# Sheet1.net
KiCad netlist of a schematic drawn in Altium Designer
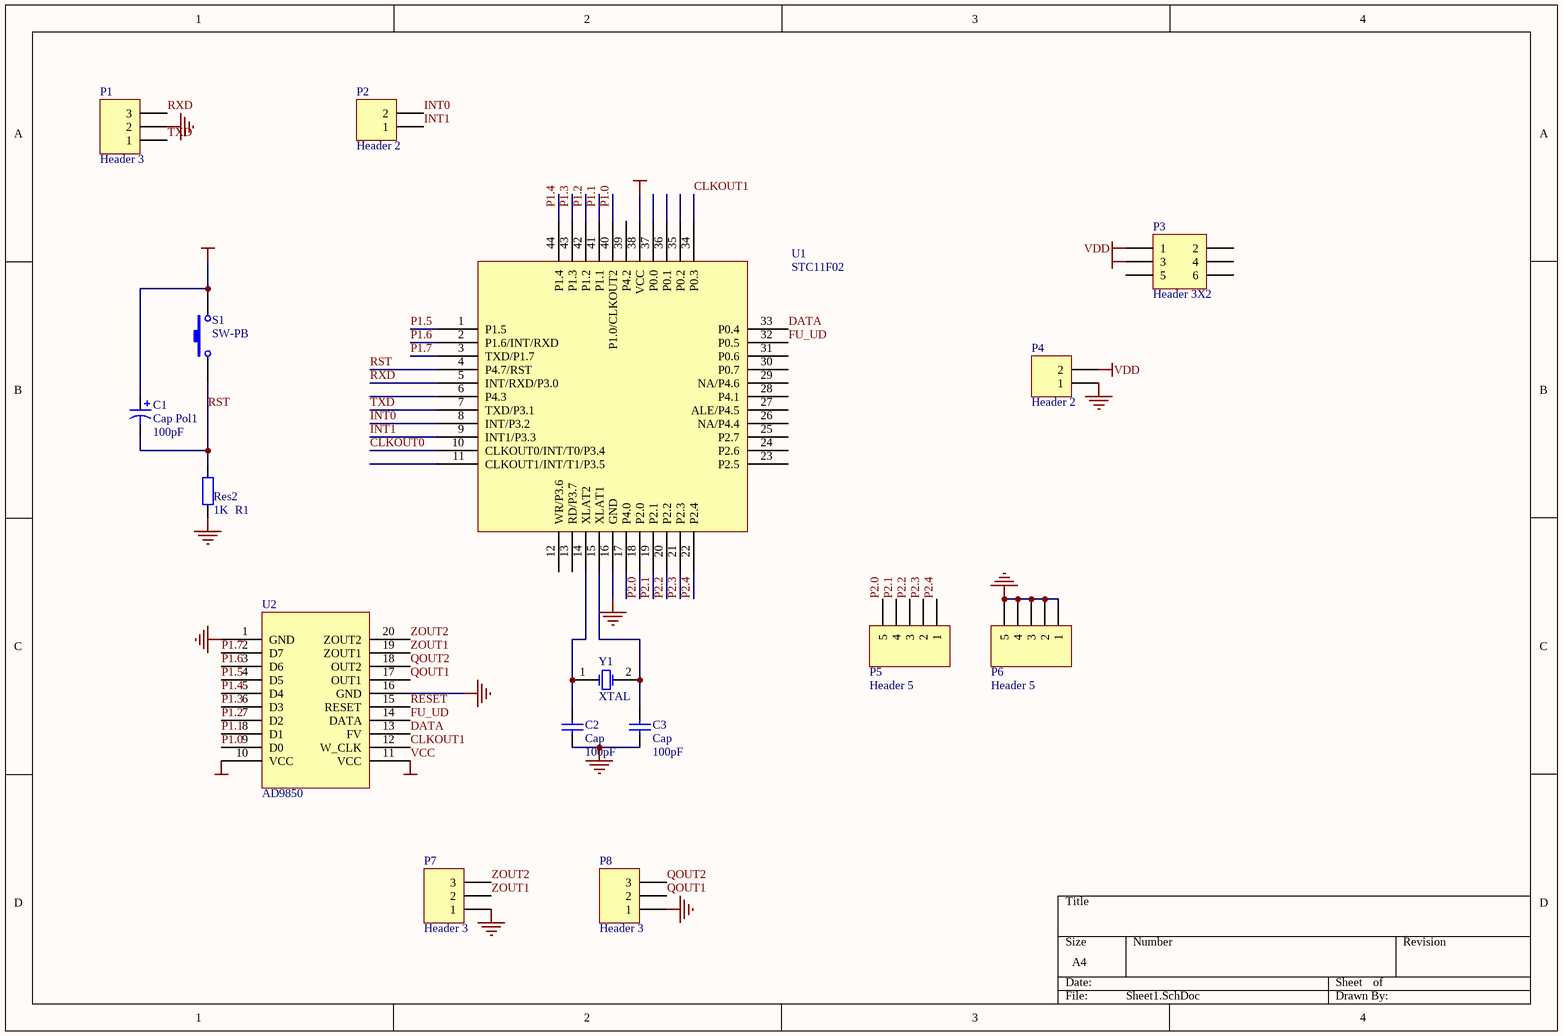
[diagram p0: Sheet1.SchDoc]

(export (version "E")
  (design (tool "Eeschema 10.0.6"))
  (components
    (comp (ref "C1")
      (value "Cap Pol1")
      (footprint "3.5X2.8X1.9")
      (description "Polarized Capacitor (Radial)")
      (fields (field (name "ALTIUM_VALUE") "100pF") (field (name "PUBLISHER") "Altium Limited"))
      (libsource (lib "Miscellaneous Devices") (part "Cap Pol1"))
    )
    (comp (ref "C2")
      (value "Cap")
      (footprint "2012[0805]")
      (description "Capacitor")
      (fields (field (name "ALTIUM_VALUE") "100pF") (field (name "PUBLISHER") "Altium Limited"))
      (libsource (lib "Miscellaneous Devices") (part "Cap"))
    )
    (comp (ref "C3")
      (value "Cap")
      (footprint "6-0805")
      (description "Capacitor")
      (fields (field (name "ALTIUM_VALUE") "100pF") (field (name "PUBLISHER") "Altium Limited"))
      (libsource (lib "Miscellaneous Devices") (part "Cap"))
    )
    (comp (ref "P1")
      (value "Header 3")
      (footprint "HDR1X3")
      (description "Header, 3-Pin")
      (fields (field (name "PUBLISHER") "Altium Limited"))
      (libsource (lib "Miscellaneous Connectors") (part "Header 3"))
    )
    (comp (ref "P2")
      (value "Header 2")
      (footprint "HDR1X2")
      (description "Header, 2-Pin")
      (fields (field (name "PUBLISHER") "Altium Limited"))
      (libsource (lib "Miscellaneous Connectors") (part "Header 2"))
    )
    (comp (ref "P3")
      (value "Header 3X2")
      (footprint "KZ")
      (description "Header, 3-Pin, Dual row")
      (fields (field (name "PUBLISHER") "Altium Limited"))
      (libsource (lib "Miscellaneous Connectors") (part "Header 3X2"))
    )
    (comp (ref "P4")
      (value "Header 2")
      (footprint "HDR1X2")
      (description "Header, 2-Pin")
      (fields (field (name "PUBLISHER") "Altium Limited"))
      (libsource (lib "Miscellaneous Connectors") (part "Header 2"))
    )
    (comp (ref "P5")
      (value "Header 5")
      (footprint "HDR1X5")
      (description "Header, 5-Pin")
      (fields (field (name "PUBLISHER") "Altium Limited"))
      (libsource (lib "Miscellaneous Connectors") (part "Header 5"))
    )
    (comp (ref "P6")
      (value "Header 5")
      (footprint "HDR1X5")
      (description "Header, 5-Pin")
      (fields (field (name "PUBLISHER") "Altium Limited"))
      (libsource (lib "Miscellaneous Connectors") (part "Header 5"))
    )
    (comp (ref "P7")
      (value "Header 3")
      (footprint "HDR1X3")
      (description "Header, 3-Pin")
      (fields (field (name "PUBLISHER") "Altium Limited"))
      (libsource (lib "Miscellaneous Connectors") (part "Header 3"))
    )
    (comp (ref "P8")
      (value "Header 3")
      (footprint "HDR1X3")
      (description "Header, 3-Pin")
      (fields (field (name "PUBLISHER") "Altium Limited"))
      (libsource (lib "Miscellaneous Connectors") (part "Header 3"))
    )
    (comp (ref "R1")
      (value "Res2")
      (footprint "6-0805")
      (description "Resistor")
      (fields (field (name "ALTIUM_VALUE") "1K") (field (name "PUBLISHER") "Altium Limited"))
      (libsource (lib "Miscellaneous Devices") (part "Res2"))
    )
    (comp (ref "S1")
      (value "SW-PB")
      (footprint "按键")
      (description "Switch")
      (fields (field (name "PUBLISHER") "Altium Limited"))
      (libsource (lib "Miscellaneous Devices") (part "SW-PB"))
    )
    (comp (ref "U1") (value "STC11F02") (footprint "LQLPF44") (libsource (lib "STC_sch") (part "STC11F02")))
    (comp (ref "U2") (value "AD9850") (footprint "ADMK") (libsource (lib "STC_sch") (part "AD9850")))
    (comp (ref "Y1")
      (value "XTAL")
      (footprint "XTAL-200mil")
      (description "Crystal Oscillator")
      (fields (field (name "PUBLISHER") "Altium Limited"))
      (libsource (lib "Miscellaneous Devices") (part "XTAL"))
    )
  )
  (nets
    (net (code "1") (name "+5") (class "Default")
      (node (ref "C1") (pin "1") (pinfunction "1_1") (pintype "passive"))
      (node (ref "P3") (pin "3") (pinfunction "3_3") (pintype "passive"))
      (node (ref "S1") (pin "2") (pinfunction "2_2") (pintype "passive"))
      (node (ref "U1") (pin "38") (pinfunction "VCC_38") (pintype "passive"))
      (node (ref "U2") (pin "10") (pinfunction "VCC_10") (pintype "passive"))
      (node (ref "U2") (pin "11") (pinfunction "VCC_11") (pintype "passive"))
    )
    (net (code "2") (name "/CLKOUT0") (class "Default")
      (node (ref "U1") (pin "10") (pinfunction "CLKOUT0/INT/T0/P3.4_10") (pintype "passive"))
    )
    (net (code "3") (name "/CLKOUT1") (class "Default")
      (node (ref "U1") (pin "34") (pinfunction "P0.3_34") (pintype "passive"))
      (node (ref "U2") (pin "12") (pinfunction "W_CLK_12") (pintype "passive"))
    )
    (net (code "4") (name "/DATA") (class "Default")
      (node (ref "U1") (pin "33") (pinfunction "P0.4_33") (pintype "passive"))
      (node (ref "U2") (pin "13") (pinfunction "FV_13") (pintype "passive"))
    )
    (net (code "5") (name "/FU_UD") (class "Default")
      (node (ref "U1") (pin "32") (pinfunction "P0.5_32") (pintype "passive"))
      (node (ref "U2") (pin "14") (pinfunction "DATA_14") (pintype "passive"))
    )
    (net (code "6") (name "/INT0") (class "Default")
      (node (ref "P2") (pin "2") (pinfunction "2_2") (pintype "passive"))
      (node (ref "U1") (pin "8") (pinfunction "INT/P3.2_8") (pintype "passive"))
    )
    (net (code "7") (name "/INT1") (class "Default")
      (node (ref "P2") (pin "1") (pinfunction "1_1") (pintype "passive"))
      (node (ref "U1") (pin "9") (pinfunction "INT1/P3.3_9") (pintype "passive"))
    )
    (net (code "8") (name "/P1.0") (class "Default")
      (node (ref "U1") (pin "40") (pinfunction "P1.0/CLKOUT2_40") (pintype "passive"))
      (node (ref "U2") (pin "9") (pinfunction "D0_9") (pintype "passive"))
    )
    (net (code "9") (name "/P1.1") (class "Default")
      (node (ref "U1") (pin "41") (pinfunction "P1.1_41") (pintype "passive"))
      (node (ref "U2") (pin "8") (pinfunction "D1_8") (pintype "passive"))
    )
    (net (code "10") (name "/P1.2") (class "Default")
      (node (ref "U1") (pin "42") (pinfunction "P1.2_42") (pintype "passive"))
      (node (ref "U2") (pin "7") (pinfunction "D2_7") (pintype "passive"))
    )
    (net (code "11") (name "/P1.3") (class "Default")
      (node (ref "U1") (pin "43") (pinfunction "P1.3_43") (pintype "passive"))
      (node (ref "U2") (pin "6") (pinfunction "D3_6") (pintype "passive"))
    )
    (net (code "12") (name "/P1.4") (class "Default")
      (node (ref "U1") (pin "44") (pinfunction "P1.4_44") (pintype "passive"))
      (node (ref "U2") (pin "5") (pinfunction "D4_5") (pintype "passive"))
    )
    (net (code "13") (name "/P1.5") (class "Default")
      (node (ref "U1") (pin "1") (pinfunction "P1.5_1") (pintype "passive"))
      (node (ref "U2") (pin "4") (pinfunction "D5_4") (pintype "passive"))
    )
    (net (code "14") (name "/P1.6") (class "Default")
      (node (ref "U1") (pin "2") (pinfunction "P1.6/INT/RXD_2") (pintype "passive"))
      (node (ref "U2") (pin "3") (pinfunction "D6_3") (pintype "passive"))
    )
    (net (code "15") (name "/P1.7") (class "Default")
      (node (ref "U1") (pin "3") (pinfunction "TXD/P1.7_3") (pintype "passive"))
      (node (ref "U2") (pin "2") (pinfunction "D7_2") (pintype "passive"))
    )
    (net (code "16") (name "/P2.0") (class "Default")
      (node (ref "P5") (pin "5") (pinfunction "5_5") (pintype "passive"))
      (node (ref "U1") (pin "18") (pinfunction "P2.0_18") (pintype "passive"))
    )
    (net (code "17") (name "/P2.1") (class "Default")
      (node (ref "P5") (pin "4") (pinfunction "4_4") (pintype "passive"))
      (node (ref "U1") (pin "19") (pinfunction "P2.1_19") (pintype "passive"))
    )
    (net (code "18") (name "/P2.2") (class "Default")
      (node (ref "P5") (pin "3") (pinfunction "3_3") (pintype "passive"))
      (node (ref "U1") (pin "20") (pinfunction "P2.2_20") (pintype "passive"))
    )
    (net (code "19") (name "/P2.3") (class "Default")
      (node (ref "P5") (pin "2") (pinfunction "2_2") (pintype "passive"))
      (node (ref "U1") (pin "21") (pinfunction "P2.3_21") (pintype "passive"))
    )
    (net (code "20") (name "/P2.4") (class "Default")
      (node (ref "P5") (pin "1") (pinfunction "1_1") (pintype "passive"))
      (node (ref "U1") (pin "22") (pinfunction "P2.4_22") (pintype "passive"))
    )
    (net (code "21") (name "/QOUT1") (class "Default")
      (node (ref "P8") (pin "2") (pinfunction "2_2") (pintype "passive"))
      (node (ref "U2") (pin "17") (pinfunction "OUT1_17") (pintype "passive"))
    )
    (net (code "22") (name "/QOUT2") (class "Default")
      (node (ref "P8") (pin "3") (pinfunction "3_3") (pintype "passive"))
      (node (ref "U2") (pin "18") (pinfunction "OUT2_18") (pintype "passive"))
    )
    (net (code "23") (name "/RESET") (class "Default")
      (node (ref "U2") (pin "15") (pinfunction "RESET_15") (pintype "passive"))
    )
    (net (code "24") (name "/RST") (class "Default")
      (node (ref "C1") (pin "2") (pinfunction "2_2") (pintype "passive"))
      (node (ref "R1") (pin "2") (pinfunction "2_2") (pintype "passive"))
      (node (ref "S1") (pin "1") (pinfunction "1_1") (pintype "passive"))
      (node (ref "U1") (pin "4") (pinfunction "P4.7/RST_4") (pintype "passive"))
    )
    (net (code "25") (name "/RXD") (class "Default")
      (node (ref "P1") (pin "3") (pinfunction "3_3") (pintype "passive"))
      (node (ref "U1") (pin "5") (pinfunction "INT/RXD/P3.0_5") (pintype "passive"))
    )
    (net (code "26") (name "/TXD") (class "Default")
      (node (ref "P1") (pin "1") (pinfunction "1_1") (pintype "passive"))
      (node (ref "U1") (pin "7") (pinfunction "TXD/P3.1_7") (pintype "passive"))
    )
    (net (code "27") (name "/ZOUT1") (class "Default")
      (node (ref "P7") (pin "2") (pinfunction "2_2") (pintype "passive"))
      (node (ref "U2") (pin "19") (pinfunction "ZOUT1_19") (pintype "passive"))
    )
    (net (code "28") (name "/ZOUT2") (class "Default")
      (node (ref "P7") (pin "3") (pinfunction "3_3") (pintype "passive"))
      (node (ref "U2") (pin "20") (pinfunction "ZOUT2_20") (pintype "passive"))
    )
    (net (code "29") (name "GND") (class "Default")
      (node (ref "C2") (pin "1") (pinfunction "1_1") (pintype "passive"))
      (node (ref "C3") (pin "1") (pinfunction "1_1") (pintype "passive"))
      (node (ref "P1") (pin "2") (pinfunction "2_2") (pintype "passive"))
      (node (ref "P4") (pin "1") (pinfunction "1_1") (pintype "passive"))
      (node (ref "P6") (pin "1") (pinfunction "1_1") (pintype "passive"))
      (node (ref "P6") (pin "2") (pinfunction "2_2") (pintype "passive"))
      (node (ref "P6") (pin "3") (pinfunction "3_3") (pintype "passive"))
      (node (ref "P6") (pin "4") (pinfunction "4_4") (pintype "passive"))
      (node (ref "P6") (pin "5") (pinfunction "5_5") (pintype "passive"))
      (node (ref "P7") (pin "1") (pinfunction "1_1") (pintype "passive"))
      (node (ref "P8") (pin "1") (pinfunction "1_1") (pintype "passive"))
      (node (ref "R1") (pin "1") (pinfunction "1_1") (pintype "passive"))
      (node (ref "U1") (pin "16") (pinfunction "GND_16") (pintype "passive"))
      (node (ref "U2") (pin "1") (pinfunction "GND_1") (pintype "passive"))
      (node (ref "U2") (pin "16") (pinfunction "GND_16") (pintype "passive"))
    )
    (net (code "30") (name "Net-(U1-XLAT1)") (class "Default")
      (node (ref "C3") (pin "2") (pinfunction "2_2") (pintype "passive"))
      (node (ref "U1") (pin "15") (pinfunction "XLAT1_15") (pintype "passive"))
      (node (ref "Y1") (pin "2") (pinfunction "OSC2_2") (pintype "passive"))
    )
    (net (code "31") (name "Net-(U1-XLAT2)") (class "Default")
      (node (ref "C2") (pin "2") (pinfunction "2_2") (pintype "passive"))
      (node (ref "U1") (pin "14") (pinfunction "XLAT2_14") (pintype "passive"))
      (node (ref "Y1") (pin "1") (pinfunction "OSC1_1") (pintype "passive"))
    )
    (net (code "32") (name "VDD") (class "Default")
      (node (ref "P3") (pin "1") (pinfunction "1_1") (pintype "passive"))
      (node (ref "P4") (pin "2") (pinfunction "2_2") (pintype "passive"))
    )
    (net (code "33") (name "unconnected-(P3-Pad2)") (class "Default")
      (node (ref "P3") (pin "2") (pinfunction "2_2") (pintype "passive"))
    )
    (net (code "34") (name "unconnected-(P3-Pad4)") (class "Default")
      (node (ref "P3") (pin "4") (pinfunction "4_4") (pintype "passive"))
    )
    (net (code "35") (name "unconnected-(P3-Pad5)") (class "Default")
      (node (ref "P3") (pin "5") (pinfunction "5_5") (pintype "passive"))
    )
    (net (code "36") (name "unconnected-(P3-Pad6)") (class "Default")
      (node (ref "P3") (pin "6") (pinfunction "6_6") (pintype "passive"))
    )
    (net (code "37") (name "unconnected-(U1-ALE{slash}P4.5-Pad27)") (class "Default")
      (node (ref "U1") (pin "27") (pinfunction "ALE/P4.5_27") (pintype "passive"))
    )
    (net (code "38") (name "unconnected-(U1-CLKOUT1{slash}INT{slash}T1{slash}P3.5-Pad11)") (class "Default")
      (node (ref "U1") (pin "11") (pinfunction "CLKOUT1/INT/T1/P3.5_11") (pintype "passive"))
    )
    (net (code "39") (name "unconnected-(U1-NA{slash}P4.4-Pad26)") (class "Default")
      (node (ref "U1") (pin "26") (pinfunction "NA/P4.4_26") (pintype "passive"))
    )
    (net (code "40") (name "unconnected-(U1-NA{slash}P4.6-Pad29)") (class "Default")
      (node (ref "U1") (pin "29") (pinfunction "NA/P4.6_29") (pintype "passive"))
    )
    (net (code "41") (name "unconnected-(U1-P0.0-Pad37)") (class "Default")
      (node (ref "U1") (pin "37") (pinfunction "P0.0_37") (pintype "passive"))
    )
    (net (code "42") (name "unconnected-(U1-P0.1-Pad36)") (class "Default")
      (node (ref "U1") (pin "36") (pinfunction "P0.1_36") (pintype "passive"))
    )
    (net (code "43") (name "unconnected-(U1-P0.2-Pad35)") (class "Default")
      (node (ref "U1") (pin "35") (pinfunction "P0.2_35") (pintype "passive"))
    )
    (net (code "44") (name "unconnected-(U1-P0.6-Pad31)") (class "Default")
      (node (ref "U1") (pin "31") (pinfunction "P0.6_31") (pintype "passive"))
    )
    (net (code "45") (name "unconnected-(U1-P0.7-Pad30)") (class "Default")
      (node (ref "U1") (pin "30") (pinfunction "P0.7_30") (pintype "passive"))
    )
    (net (code "46") (name "unconnected-(U1-P2.5-Pad23)") (class "Default")
      (node (ref "U1") (pin "23") (pinfunction "P2.5_23") (pintype "passive"))
    )
    (net (code "47") (name "unconnected-(U1-P2.6-Pad24)") (class "Default")
      (node (ref "U1") (pin "24") (pinfunction "P2.6_24") (pintype "passive"))
    )
    (net (code "48") (name "unconnected-(U1-P2.7-Pad25)") (class "Default")
      (node (ref "U1") (pin "25") (pinfunction "P2.7_25") (pintype "passive"))
    )
    (net (code "49") (name "unconnected-(U1-P4.0-Pad17)") (class "Default")
      (node (ref "U1") (pin "17") (pinfunction "P4.0_17") (pintype "passive"))
    )
    (net (code "50") (name "unconnected-(U1-P4.1-Pad28)") (class "Default")
      (node (ref "U1") (pin "28") (pinfunction "P4.1_28") (pintype "passive"))
    )
    (net (code "51") (name "unconnected-(U1-P4.2-Pad39)") (class "Default")
      (node (ref "U1") (pin "39") (pinfunction "P4.2_39") (pintype "passive"))
    )
    (net (code "52") (name "unconnected-(U1-P4.3-Pad6)") (class "Default")
      (node (ref "U1") (pin "6") (pinfunction "P4.3_6") (pintype "passive"))
    )
    (net (code "53") (name "unconnected-(U1-RD{slash}P3.7-Pad13)") (class "Default")
      (node (ref "U1") (pin "13") (pinfunction "RD/P3.7_13") (pintype "passive"))
    )
    (net (code "54") (name "unconnected-(U1-WR{slash}P3.6-Pad12)") (class "Default")
      (node (ref "U1") (pin "12") (pinfunction "WR/P3.6_12") (pintype "passive"))
    )
  )
)
